# SCH_Trabalho-AP1-Somador_2024-10-15.net
KiCad netlist of a schematic drawn in EasyEDA
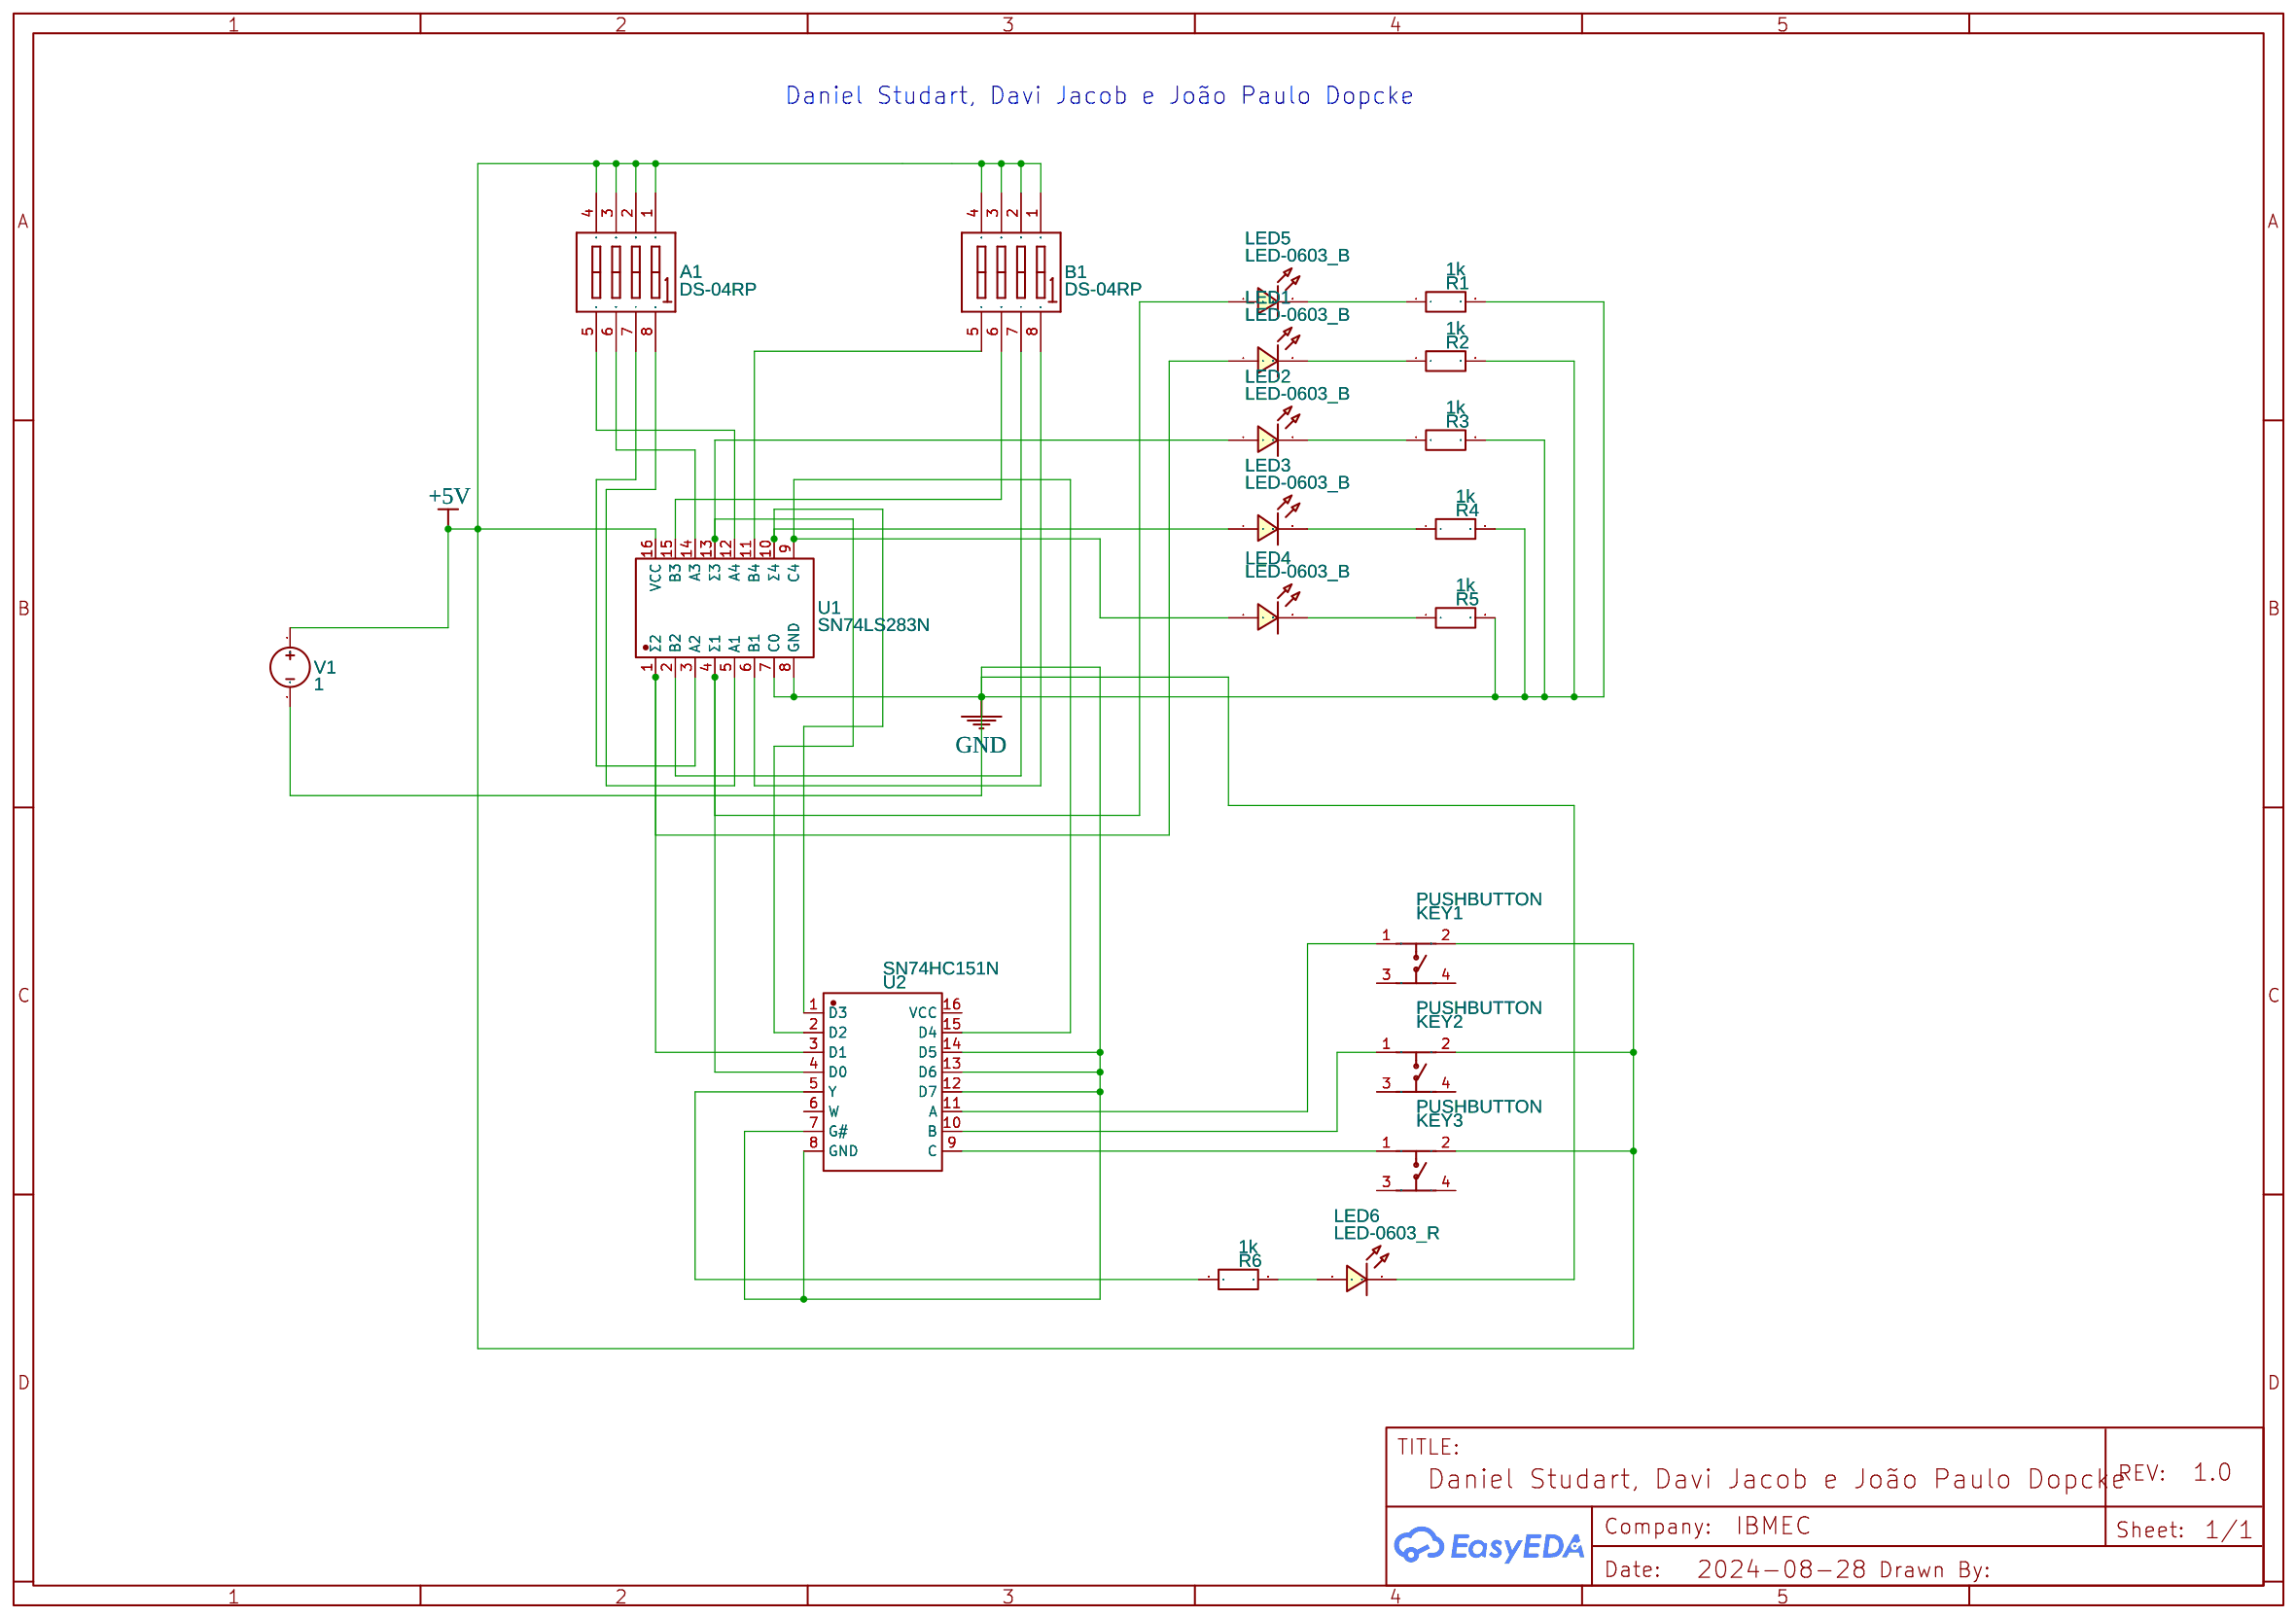
[diagram p0: schematic sheet]

(export (version "E")
  (design (tool "Eeschema 10.0.6"))
  (components
    (comp (ref "A1")
      (value "DS-04RP")
      (fields (field (name "Manufacturer") "韩国韩荣"))
      (libsource (lib "") (part "DS-04RP_1"))
    )
    (comp (ref "B1")
      (value "DS-04RP")
      (fields (field (name "Manufacturer") "韩国韩荣"))
      (libsource (lib "") (part "DS-04RP"))
    )
    (comp (ref "KEY1")
      (value "PUSHBUTTON")
      (fields (field (name "Manufacturer Part") "4pinTACTPCBTHTPushButton"))
      (libsource (lib "") (part "4PINTACTPCBTHTPUSHBUTTON"))
    )
    (comp (ref "KEY2")
      (value "PUSHBUTTON")
      (fields (field (name "Manufacturer Part") "4pinTACTPCBTHTPushButton"))
      (libsource (lib "") (part "4PINTACTPCBTHTPUSHBUTTON"))
    )
    (comp (ref "KEY3")
      (value "PUSHBUTTON")
      (fields (field (name "Manufacturer Part") "4pinTACTPCBTHTPushButton"))
      (libsource (lib "") (part "4PINTACTPCBTHTPUSHBUTTON"))
    )
    (comp (ref "LED1")
      (value "LED-0603_B")
      (fields
        (field (name "Manufacturer Part") "19-217/BHC-ZL1M2RY/3T")
        (field (name "Manufacturer") "EVERLIGHT(台湾亿光)")
      )
      (libsource (lib "") (part "LED-0603_B"))
    )
    (comp (ref "LED2")
      (value "LED-0603_B")
      (fields
        (field (name "Manufacturer Part") "19-217/BHC-ZL1M2RY/3T")
        (field (name "Manufacturer") "EVERLIGHT(台湾亿光)")
      )
      (libsource (lib "") (part "LED-0603_B"))
    )
    (comp (ref "LED3")
      (value "LED-0603_B")
      (fields
        (field (name "Manufacturer Part") "19-217/BHC-ZL1M2RY/3T")
        (field (name "Manufacturer") "EVERLIGHT(台湾亿光)")
      )
      (libsource (lib "") (part "LED-0603_B"))
    )
    (comp (ref "LED4")
      (value "LED-0603_B")
      (fields
        (field (name "Manufacturer Part") "19-217/BHC-ZL1M2RY/3T")
        (field (name "Manufacturer") "EVERLIGHT(台湾亿光)")
      )
      (libsource (lib "") (part "LED-0603_B"))
    )
    (comp (ref "LED5")
      (value "LED-0603_B")
      (fields
        (field (name "Manufacturer Part") "19-217/BHC-ZL1M2RY/3T")
        (field (name "Manufacturer") "EVERLIGHT(台湾亿光)")
      )
      (libsource (lib "") (part "LED-0603_B"))
    )
    (comp (ref "LED6")
      (value "LED-0603_R")
      (fields
        (field (name "Manufacturer Part") "19-217/R6C-AL1M2VY/3T")
        (field (name "Manufacturer") "EVERLIGHT(台湾亿光)")
      )
      (libsource (lib "") (part "LED-0603_R"))
    )
    (comp (ref "R1") (value "1k") (libsource (lib "") (part "R_0603_EU")))
    (comp (ref "R2") (value "1k") (libsource (lib "") (part "R_0603_EU")))
    (comp (ref "R3") (value "1k") (libsource (lib "") (part "R_0603_EU")))
    (comp (ref "R4") (value "1k") (libsource (lib "") (part "R_0603_EU")))
    (comp (ref "R5") (value "1k") (libsource (lib "") (part "R_0603_EU")))
    (comp (ref "R6") (value "1k") (libsource (lib "") (part "R_0603_EU")))
    (comp (ref "U1")
      (value "SN74LS283N")
      (fields (field (name "Manufacturer") "TI(德州仪器)"))
      (libsource (lib "") (part "SN74LS283N"))
    )
    (comp (ref "U2")
      (value "SN74HC151N")
      (fields (field (name "Manufacturer") "TI(德州仪器)"))
      (libsource (lib "") (part "SN74HC151N"))
    )
    (comp (ref "V1") (value "1") (libsource (lib "") (part "VDC")))
  )
  (nets
    (net (code "1") (name "+5V") (class "Default")
      (node (ref "A1") (pin "1") (pinfunction "A1_1") (pintype "input"))
      (node (ref "A1") (pin "2") (pinfunction "A2_2") (pintype "input"))
      (node (ref "A1") (pin "3") (pinfunction "A3_3") (pintype "input"))
      (node (ref "A1") (pin "4") (pinfunction "A4_4") (pintype "input"))
      (node (ref "B1") (pin "1") (pinfunction "A1_1") (pintype "input"))
      (node (ref "B1") (pin "2") (pinfunction "A2_2") (pintype "input"))
      (node (ref "B1") (pin "3") (pinfunction "A3_3") (pintype "input"))
      (node (ref "B1") (pin "4") (pinfunction "A4_4") (pintype "input"))
      (node (ref "KEY1") (pin "2") (pinfunction "2_2") (pintype "unspecified"))
      (node (ref "KEY2") (pin "2") (pinfunction "2_2") (pintype "unspecified"))
      (node (ref "KEY3") (pin "2") (pinfunction "2_2") (pintype "unspecified"))
      (node (ref "U1") (pin "16") (pinfunction "VCC_16") (pintype "unspecified"))
      (node (ref "V1") (pin "1") (pinfunction "1_1") (pintype "unspecified"))
    )
    (net (code "2") (name "GND") (class "Default")
      (node (ref "LED6") (pin "2") (pinfunction "2_2") (pintype "unspecified"))
      (node (ref "R1") (pin "2") (pinfunction "2_2") (pintype "unspecified"))
      (node (ref "R2") (pin "2") (pinfunction "2_2") (pintype "unspecified"))
      (node (ref "R3") (pin "2") (pinfunction "2_2") (pintype "unspecified"))
      (node (ref "R4") (pin "2") (pinfunction "2_2") (pintype "unspecified"))
      (node (ref "R5") (pin "2") (pinfunction "2_2") (pintype "unspecified"))
      (node (ref "U1") (pin "7") (pinfunction "C0_7") (pintype "unspecified"))
      (node (ref "U1") (pin "8") (pinfunction "GND_8") (pintype "unspecified"))
      (node (ref "U2") (pin "12") (pinfunction "D7_12") (pintype "unspecified"))
      (node (ref "U2") (pin "13") (pinfunction "D6_13") (pintype "unspecified"))
      (node (ref "U2") (pin "14") (pinfunction "D5_14") (pintype "unspecified"))
      (node (ref "U2") (pin "7") (pinfunction "G#_7") (pintype "unspecified"))
      (node (ref "U2") (pin "8") (pinfunction "GND_8") (pintype "unspecified"))
      (node (ref "V1") (pin "2") (pinfunction "2_2") (pintype "unspecified"))
    )
    (net (code "3") (name "Net-(LED1-Pad2)") (class "Default")
      (node (ref "LED1") (pin "2") (pinfunction "2_2") (pintype "unspecified"))
      (node (ref "R2") (pin "1") (pinfunction "1_1") (pintype "unspecified"))
    )
    (net (code "4") (name "Net-(LED2-Pad2)") (class "Default")
      (node (ref "LED2") (pin "2") (pinfunction "2_2") (pintype "unspecified"))
      (node (ref "R3") (pin "1") (pinfunction "1_1") (pintype "unspecified"))
    )
    (net (code "5") (name "Net-(LED3-Pad2)") (class "Default")
      (node (ref "LED3") (pin "2") (pinfunction "2_2") (pintype "unspecified"))
      (node (ref "R4") (pin "1") (pinfunction "1_1") (pintype "unspecified"))
    )
    (net (code "6") (name "Net-(LED4-Pad2)") (class "Default")
      (node (ref "LED4") (pin "2") (pinfunction "2_2") (pintype "unspecified"))
      (node (ref "R5") (pin "1") (pinfunction "1_1") (pintype "unspecified"))
    )
    (net (code "7") (name "Net-(LED5-Pad2)") (class "Default")
      (node (ref "LED5") (pin "2") (pinfunction "2_2") (pintype "unspecified"))
      (node (ref "R1") (pin "1") (pinfunction "1_1") (pintype "unspecified"))
    )
    (net (code "8") (name "Net-(LED6-Pad1)") (class "Default")
      (node (ref "LED6") (pin "1") (pinfunction "1_1") (pintype "unspecified"))
      (node (ref "R6") (pin "2") (pinfunction "2_2") (pintype "unspecified"))
    )
    (net (code "9") (name "Net-(U1-A1)") (class "Default")
      (node (ref "A1") (pin "8") (pinfunction "8_8") (pintype "input"))
      (node (ref "U1") (pin "5") (pinfunction "A1_5") (pintype "unspecified"))
    )
    (net (code "10") (name "Net-(U1-A2)") (class "Default")
      (node (ref "A1") (pin "7") (pinfunction "7_7") (pintype "input"))
      (node (ref "U1") (pin "3") (pinfunction "A2_3") (pintype "unspecified"))
    )
    (net (code "11") (name "Net-(U1-A3)") (class "Default")
      (node (ref "A1") (pin "6") (pinfunction "6_6") (pintype "input"))
      (node (ref "U1") (pin "14") (pinfunction "A3_14") (pintype "unspecified"))
    )
    (net (code "12") (name "Net-(U1-A4)") (class "Default")
      (node (ref "A1") (pin "5") (pinfunction "5_5") (pintype "input"))
      (node (ref "U1") (pin "12") (pinfunction "A4_12") (pintype "unspecified"))
    )
    (net (code "13") (name "Net-(U1-B1)") (class "Default")
      (node (ref "B1") (pin "8") (pinfunction "8_8") (pintype "input"))
      (node (ref "U1") (pin "6") (pinfunction "B1_6") (pintype "unspecified"))
    )
    (net (code "14") (name "Net-(U1-B2)") (class "Default")
      (node (ref "B1") (pin "7") (pinfunction "7_7") (pintype "input"))
      (node (ref "U1") (pin "2") (pinfunction "B2_2") (pintype "unspecified"))
    )
    (net (code "15") (name "Net-(U1-B3)") (class "Default")
      (node (ref "B1") (pin "6") (pinfunction "6_6") (pintype "input"))
      (node (ref "U1") (pin "15") (pinfunction "B3_15") (pintype "unspecified"))
    )
    (net (code "16") (name "Net-(U1-B4)") (class "Default")
      (node (ref "B1") (pin "5") (pinfunction "5_5") (pintype "input"))
      (node (ref "U1") (pin "11") (pinfunction "B4_11") (pintype "unspecified"))
    )
    (net (code "17") (name "Net-(U1-C4)") (class "Default")
      (node (ref "LED4") (pin "1") (pinfunction "1_1") (pintype "unspecified"))
      (node (ref "U1") (pin "9") (pinfunction "C4_9") (pintype "unspecified"))
      (node (ref "U2") (pin "15") (pinfunction "D4_15") (pintype "unspecified"))
    )
    (net (code "18") (name "Net-(U1-Σ1)") (class "Default")
      (node (ref "LED5") (pin "1") (pinfunction "1_1") (pintype "unspecified"))
      (node (ref "U1") (pin "4") (pinfunction "Σ1_4") (pintype "unspecified"))
      (node (ref "U2") (pin "4") (pinfunction "D0_4") (pintype "unspecified"))
    )
    (net (code "19") (name "Net-(U1-Σ2)") (class "Default")
      (node (ref "LED1") (pin "1") (pinfunction "1_1") (pintype "unspecified"))
      (node (ref "U1") (pin "1") (pinfunction "Σ2_1") (pintype "unspecified"))
      (node (ref "U2") (pin "3") (pinfunction "D1_3") (pintype "unspecified"))
    )
    (net (code "20") (name "Net-(U1-Σ3)") (class "Default")
      (node (ref "LED2") (pin "1") (pinfunction "1_1") (pintype "unspecified"))
      (node (ref "U1") (pin "13") (pinfunction "Σ3_13") (pintype "unspecified"))
      (node (ref "U2") (pin "2") (pinfunction "D2_2") (pintype "unspecified"))
    )
    (net (code "21") (name "Net-(U1-Σ4)") (class "Default")
      (node (ref "LED3") (pin "1") (pinfunction "1_1") (pintype "unspecified"))
      (node (ref "U1") (pin "10") (pinfunction "Σ4_10") (pintype "unspecified"))
      (node (ref "U2") (pin "1") (pinfunction "D3_1") (pintype "unspecified"))
    )
    (net (code "22") (name "Net-(U2-A)") (class "Default")
      (node (ref "KEY1") (pin "1") (pinfunction "1_1") (pintype "unspecified"))
      (node (ref "U2") (pin "11") (pinfunction "A_11") (pintype "unspecified"))
    )
    (net (code "23") (name "Net-(U2-B)") (class "Default")
      (node (ref "KEY2") (pin "1") (pinfunction "1_1") (pintype "unspecified"))
      (node (ref "U2") (pin "10") (pinfunction "B_10") (pintype "unspecified"))
    )
    (net (code "24") (name "Net-(U2-C)") (class "Default")
      (node (ref "KEY3") (pin "1") (pinfunction "1_1") (pintype "unspecified"))
      (node (ref "U2") (pin "9") (pinfunction "C_9") (pintype "unspecified"))
    )
    (net (code "25") (name "Net-(U2-Y)") (class "Default")
      (node (ref "R6") (pin "1") (pinfunction "1_1") (pintype "unspecified"))
      (node (ref "U2") (pin "5") (pinfunction "Y_5") (pintype "unspecified"))
    )
    (net (code "26") (name "unconnected-(KEY1-Pad3)") (class "Default")
      (node (ref "KEY1") (pin "3") (pinfunction "3_3") (pintype "unspecified"))
    )
    (net (code "27") (name "unconnected-(KEY1-Pad4)") (class "Default")
      (node (ref "KEY1") (pin "4") (pinfunction "4_4") (pintype "unspecified"))
    )
    (net (code "28") (name "unconnected-(KEY2-Pad3)") (class "Default")
      (node (ref "KEY2") (pin "3") (pinfunction "3_3") (pintype "unspecified"))
    )
    (net (code "29") (name "unconnected-(KEY2-Pad4)") (class "Default")
      (node (ref "KEY2") (pin "4") (pinfunction "4_4") (pintype "unspecified"))
    )
    (net (code "30") (name "unconnected-(KEY3-Pad3)") (class "Default")
      (node (ref "KEY3") (pin "3") (pinfunction "3_3") (pintype "unspecified"))
    )
    (net (code "31") (name "unconnected-(KEY3-Pad4)") (class "Default")
      (node (ref "KEY3") (pin "4") (pinfunction "4_4") (pintype "unspecified"))
    )
    (net (code "32") (name "unconnected-(U2-VCC-Pad16)") (class "Default")
      (node (ref "U2") (pin "16") (pinfunction "VCC_16") (pintype "unspecified"))
    )
    (net (code "33") (name "unconnected-(U2-W-Pad6)") (class "Default")
      (node (ref "U2") (pin "6") (pinfunction "W_6") (pintype "unspecified"))
    )
  )
)
